# DebounceEncoder.net
KiCad netlist of a schematic drawn in EAGLE
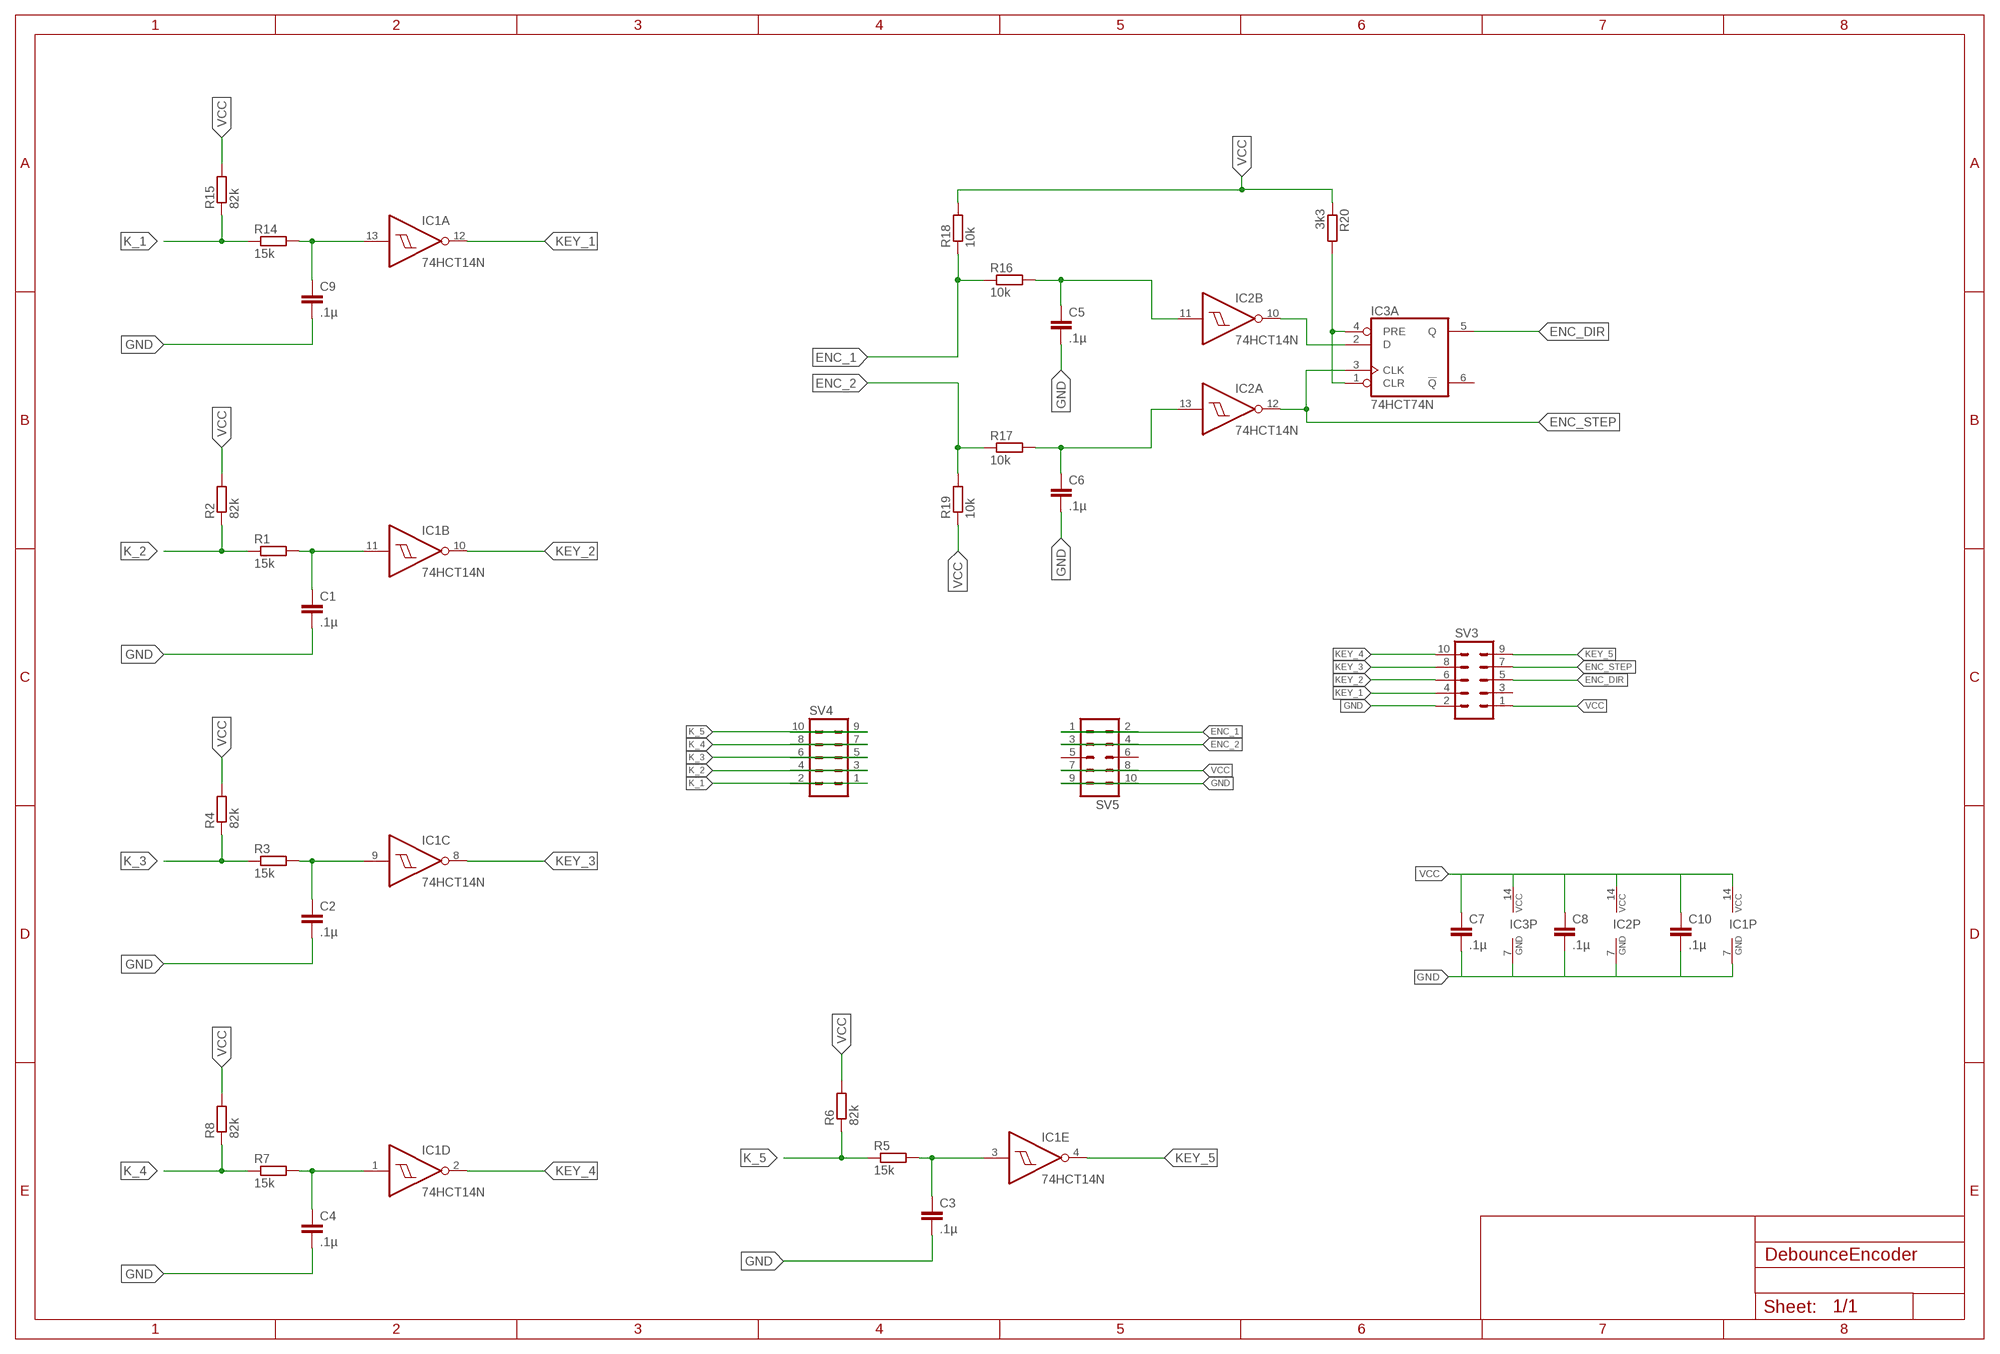
[diagram p0: schematic, sheet 1]

(export (version "E")
  (design (tool "Eeschema 10.0.6"))
  (components
    (comp (ref "C1")
      (value ".1µ")
      (footprint "eagle-import:C025-024X044")
      (libsource (lib "eagle-import") (part "C-EU025-024X044"))
    )
    (comp (ref "C2")
      (value ".1µ")
      (footprint "eagle-import:C025-024X044")
      (libsource (lib "eagle-import") (part "C-EU025-024X044"))
    )
    (comp (ref "C3")
      (value ".1µ")
      (footprint "eagle-import:C025-024X044")
      (libsource (lib "eagle-import") (part "C-EU025-024X044"))
    )
    (comp (ref "C4")
      (value ".1µ")
      (footprint "eagle-import:C025-024X044")
      (libsource (lib "eagle-import") (part "C-EU025-024X044"))
    )
    (comp (ref "C5")
      (value ".1µ")
      (footprint "eagle-import:C025-024X044")
      (libsource (lib "eagle-import") (part "C-EU025-024X044"))
    )
    (comp (ref "C6")
      (value ".1µ")
      (footprint "eagle-import:C025-024X044")
      (libsource (lib "eagle-import") (part "C-EU025-024X044"))
    )
    (comp (ref "C7")
      (value ".1µ")
      (footprint "eagle-import:C025-024X044")
      (libsource (lib "eagle-import") (part "C-EU025-024X044"))
    )
    (comp (ref "C8")
      (value ".1µ")
      (footprint "eagle-import:C025-024X044")
      (libsource (lib "eagle-import") (part "C-EU025-024X044"))
    )
    (comp (ref "C9")
      (value ".1µ")
      (footprint "eagle-import:C025-024X044")
      (libsource (lib "eagle-import") (part "C-EU025-024X044"))
    )
    (comp (ref "C10")
      (value ".1µ")
      (footprint "eagle-import:C025-024X044")
      (libsource (lib "eagle-import") (part "C-EU025-024X044"))
    )
    (comp (ref "IC1")
      (value "74HCT14N")
      (footprint "eagle-import:DIL14")
      (libsource (lib "eagle-import") (part "7414NHCT"))
    )
    (comp (ref "IC2")
      (value "74HCT14N")
      (footprint "eagle-import:DIL14")
      (libsource (lib "eagle-import") (part "7414NHCT"))
    )
    (comp (ref "IC3")
      (value "74HCT74N")
      (footprint "eagle-import:DIL14")
      (libsource (lib "eagle-import") (part "7474NHCT"))
    )
    (comp (ref "R1")
      (value "15k")
      (footprint "eagle-import:0204_7")
      (libsource (lib "eagle-import") (part "R-EU_0204/7"))
    )
    (comp (ref "R2")
      (value "82k")
      (footprint "eagle-import:0204_7")
      (libsource (lib "eagle-import") (part "R-EU_0204/7"))
    )
    (comp (ref "R3")
      (value "15k")
      (footprint "eagle-import:0204_7")
      (libsource (lib "eagle-import") (part "R-EU_0204/7"))
    )
    (comp (ref "R4")
      (value "82k")
      (footprint "eagle-import:0204_7")
      (libsource (lib "eagle-import") (part "R-EU_0204/7"))
    )
    (comp (ref "R5")
      (value "15k")
      (footprint "eagle-import:0204_7")
      (libsource (lib "eagle-import") (part "R-EU_0204/7"))
    )
    (comp (ref "R6")
      (value "82k")
      (footprint "eagle-import:0204_7")
      (libsource (lib "eagle-import") (part "R-EU_0204/7"))
    )
    (comp (ref "R7")
      (value "15k")
      (footprint "eagle-import:0204_7")
      (libsource (lib "eagle-import") (part "R-EU_0204/7"))
    )
    (comp (ref "R8")
      (value "82k")
      (footprint "eagle-import:0204_7")
      (libsource (lib "eagle-import") (part "R-EU_0204/7"))
    )
    (comp (ref "R14")
      (value "15k")
      (footprint "eagle-import:0204_7")
      (libsource (lib "eagle-import") (part "R-EU_0204/7"))
    )
    (comp (ref "R15")
      (value "82k")
      (footprint "eagle-import:0204_7")
      (libsource (lib "eagle-import") (part "R-EU_0204/7"))
    )
    (comp (ref "R16")
      (value "10k")
      (footprint "eagle-import:0204_7")
      (libsource (lib "eagle-import") (part "R-EU_0204/7"))
    )
    (comp (ref "R17")
      (value "10k")
      (footprint "eagle-import:0204_7")
      (libsource (lib "eagle-import") (part "R-EU_0204/7"))
    )
    (comp (ref "R18")
      (value "10k")
      (footprint "eagle-import:0204_7")
      (libsource (lib "eagle-import") (part "R-EU_0204/7"))
    )
    (comp (ref "R19")
      (value "10k")
      (footprint "eagle-import:0204_7")
      (libsource (lib "eagle-import") (part "R-EU_0204/7"))
    )
    (comp (ref "R20")
      (value "3k3")
      (footprint "eagle-import:0204_7")
      (libsource (lib "eagle-import") (part "R-EU_0204/7"))
    )
    (comp (ref "SV3")
      (value "ML10L")
      (footprint "eagle-import:ML10L")
      (libsource (lib "eagle-import") (part "ML10L"))
    )
    (comp (ref "SV4")
      (value "MA05-2")
      (footprint "eagle-import:MA05-2")
      (libsource (lib "eagle-import") (part "MA05-2"))
    )
    (comp (ref "SV5")
      (value "MA05-2")
      (footprint "eagle-import:MA05-2")
      (libsource (lib "eagle-import") (part "MA05-2"))
    )
  )
  (nets
    (net (code "1") (name "ENC_1") (class "Default")
      (node (ref "R16") (pin "1") (pinfunction "1_1") (pintype "passive"))
      (node (ref "R18") (pin "1") (pinfunction "1_1") (pintype "passive"))
      (node (ref "SV5") (pin "1") (pinfunction "1_1") (pintype "passive"))
      (node (ref "SV5") (pin "2") (pinfunction "2_2") (pintype "passive"))
    )
    (net (code "2") (name "ENC_2") (class "Default")
      (node (ref "R17") (pin "1") (pinfunction "1_1") (pintype "passive"))
      (node (ref "R19") (pin "2") (pinfunction "2_2") (pintype "passive"))
      (node (ref "SV5") (pin "3") (pinfunction "3_3") (pintype "passive"))
      (node (ref "SV5") (pin "4") (pinfunction "4_4") (pintype "passive"))
    )
    (net (code "3") (name "ENC_DIR") (class "Default")
      (node (ref "IC3") (pin "5") (pinfunction "Q_5") (pintype "output"))
      (node (ref "SV3") (pin "5") (pinfunction "5_5") (pintype "passive"))
    )
    (net (code "4") (name "ENC_STEP") (class "Default")
      (node (ref "IC2") (pin "12") (pinfunction "O_12") (pintype "output"))
      (node (ref "IC3") (pin "3") (pinfunction "CLK_3") (pintype "input"))
      (node (ref "SV3") (pin "7") (pinfunction "7_7") (pintype "passive"))
    )
    (net (code "5") (name "GND") (class "Default")
      (node (ref "C1") (pin "2") (pinfunction "2_2") (pintype "passive"))
      (node (ref "C10") (pin "2") (pinfunction "2_2") (pintype "passive"))
      (node (ref "C2") (pin "2") (pinfunction "2_2") (pintype "passive"))
      (node (ref "C3") (pin "2") (pinfunction "2_2") (pintype "passive"))
      (node (ref "C4") (pin "2") (pinfunction "2_2") (pintype "passive"))
      (node (ref "C5") (pin "2") (pinfunction "2_2") (pintype "passive"))
      (node (ref "C6") (pin "2") (pinfunction "2_2") (pintype "passive"))
      (node (ref "C7") (pin "2") (pinfunction "2_2") (pintype "passive"))
      (node (ref "C8") (pin "2") (pinfunction "2_2") (pintype "passive"))
      (node (ref "C9") (pin "2") (pinfunction "2_2") (pintype "passive"))
      (node (ref "IC1") (pin "7") (pinfunction "GND_7") (pintype "power_in"))
      (node (ref "IC2") (pin "7") (pinfunction "GND_7") (pintype "power_in"))
      (node (ref "IC3") (pin "7") (pinfunction "GND_7") (pintype "power_in"))
      (node (ref "SV3") (pin "2") (pinfunction "2_2") (pintype "passive"))
      (node (ref "SV5") (pin "10") (pinfunction "10_10") (pintype "passive"))
      (node (ref "SV5") (pin "9") (pinfunction "9_9") (pintype "passive"))
    )
    (net (code "6") (name "KEY_1") (class "Default")
      (node (ref "IC1") (pin "12") (pinfunction "O_12") (pintype "output"))
      (node (ref "SV3") (pin "4") (pinfunction "4_4") (pintype "passive"))
    )
    (net (code "7") (name "KEY_2") (class "Default")
      (node (ref "IC1") (pin "10") (pinfunction "O_10") (pintype "output"))
      (node (ref "SV3") (pin "6") (pinfunction "6_6") (pintype "passive"))
    )
    (net (code "8") (name "KEY_3") (class "Default")
      (node (ref "IC1") (pin "8") (pinfunction "O_8") (pintype "output"))
      (node (ref "SV3") (pin "8") (pinfunction "8_8") (pintype "passive"))
    )
    (net (code "9") (name "KEY_4") (class "Default")
      (node (ref "IC1") (pin "2") (pinfunction "O_2") (pintype "output"))
      (node (ref "SV3") (pin "10") (pinfunction "10_10") (pintype "passive"))
    )
    (net (code "10") (name "KEY_5") (class "Default")
      (node (ref "IC1") (pin "4") (pinfunction "O_4") (pintype "output"))
      (node (ref "SV3") (pin "9") (pinfunction "9_9") (pintype "passive"))
    )
    (net (code "11") (name "K_1") (class "Default")
      (node (ref "R14") (pin "1") (pinfunction "1_1") (pintype "passive"))
      (node (ref "R15") (pin "1") (pinfunction "1_1") (pintype "passive"))
      (node (ref "SV4") (pin "1") (pinfunction "1_1") (pintype "passive"))
      (node (ref "SV4") (pin "2") (pinfunction "2_2") (pintype "passive"))
    )
    (net (code "12") (name "K_2") (class "Default")
      (node (ref "R1") (pin "1") (pinfunction "1_1") (pintype "passive"))
      (node (ref "R2") (pin "1") (pinfunction "1_1") (pintype "passive"))
      (node (ref "SV4") (pin "3") (pinfunction "3_3") (pintype "passive"))
      (node (ref "SV4") (pin "4") (pinfunction "4_4") (pintype "passive"))
    )
    (net (code "13") (name "K_3") (class "Default")
      (node (ref "R3") (pin "1") (pinfunction "1_1") (pintype "passive"))
      (node (ref "R4") (pin "1") (pinfunction "1_1") (pintype "passive"))
      (node (ref "SV4") (pin "5") (pinfunction "5_5") (pintype "passive"))
      (node (ref "SV4") (pin "6") (pinfunction "6_6") (pintype "passive"))
    )
    (net (code "14") (name "K_4") (class "Default")
      (node (ref "R7") (pin "1") (pinfunction "1_1") (pintype "passive"))
      (node (ref "R8") (pin "1") (pinfunction "1_1") (pintype "passive"))
      (node (ref "SV4") (pin "7") (pinfunction "7_7") (pintype "passive"))
      (node (ref "SV4") (pin "8") (pinfunction "8_8") (pintype "passive"))
    )
    (net (code "15") (name "K_5") (class "Default")
      (node (ref "R5") (pin "1") (pinfunction "1_1") (pintype "passive"))
      (node (ref "R6") (pin "1") (pinfunction "1_1") (pintype "passive"))
      (node (ref "SV4") (pin "10") (pinfunction "10_10") (pintype "passive"))
      (node (ref "SV4") (pin "9") (pinfunction "9_9") (pintype "passive"))
    )
    (net (code "16") (name "Net-(IC1A-I)") (class "Default")
      (node (ref "C9") (pin "1") (pinfunction "1_1") (pintype "passive"))
      (node (ref "IC1") (pin "13") (pinfunction "I_13") (pintype "input"))
      (node (ref "R14") (pin "2") (pinfunction "2_2") (pintype "passive"))
    )
    (net (code "17") (name "Net-(IC1B-I)") (class "Default")
      (node (ref "C1") (pin "1") (pinfunction "1_1") (pintype "passive"))
      (node (ref "IC1") (pin "11") (pinfunction "I_11") (pintype "input"))
      (node (ref "R1") (pin "2") (pinfunction "2_2") (pintype "passive"))
    )
    (net (code "18") (name "Net-(IC1C-I)") (class "Default")
      (node (ref "C2") (pin "1") (pinfunction "1_1") (pintype "passive"))
      (node (ref "IC1") (pin "9") (pinfunction "I_9") (pintype "input"))
      (node (ref "R3") (pin "2") (pinfunction "2_2") (pintype "passive"))
    )
    (net (code "19") (name "Net-(IC1D-I)") (class "Default")
      (node (ref "C4") (pin "1") (pinfunction "1_1") (pintype "passive"))
      (node (ref "IC1") (pin "1") (pinfunction "I_1") (pintype "input"))
      (node (ref "R7") (pin "2") (pinfunction "2_2") (pintype "passive"))
    )
    (net (code "20") (name "Net-(IC1E-I)") (class "Default")
      (node (ref "C3") (pin "1") (pinfunction "1_1") (pintype "passive"))
      (node (ref "IC1") (pin "3") (pinfunction "I_3") (pintype "input"))
      (node (ref "R5") (pin "2") (pinfunction "2_2") (pintype "passive"))
    )
    (net (code "21") (name "Net-(IC2A-I)") (class "Default")
      (node (ref "C6") (pin "1") (pinfunction "1_1") (pintype "passive"))
      (node (ref "IC2") (pin "13") (pinfunction "I_13") (pintype "input"))
      (node (ref "R17") (pin "2") (pinfunction "2_2") (pintype "passive"))
    )
    (net (code "22") (name "Net-(IC2B-I)") (class "Default")
      (node (ref "C5") (pin "1") (pinfunction "1_1") (pintype "passive"))
      (node (ref "IC2") (pin "11") (pinfunction "I_11") (pintype "input"))
      (node (ref "R16") (pin "2") (pinfunction "2_2") (pintype "passive"))
    )
    (net (code "23") (name "Net-(IC2B-O)") (class "Default")
      (node (ref "IC2") (pin "10") (pinfunction "O_10") (pintype "output"))
      (node (ref "IC3") (pin "2") (pinfunction "D_2") (pintype "input"))
    )
    (net (code "24") (name "Net-(IC3A-CLR)") (class "Default")
      (node (ref "IC3") (pin "1") (pinfunction "CLR_1") (pintype "input"))
      (node (ref "IC3") (pin "4") (pinfunction "PRE_4") (pintype "input"))
      (node (ref "R20") (pin "2") (pinfunction "2_2") (pintype "passive"))
    )
    (net (code "25") (name "VCC") (class "Default")
      (node (ref "C10") (pin "1") (pinfunction "1_1") (pintype "passive"))
      (node (ref "C7") (pin "1") (pinfunction "1_1") (pintype "passive"))
      (node (ref "C8") (pin "1") (pinfunction "1_1") (pintype "passive"))
      (node (ref "IC1") (pin "14") (pinfunction "VCC_14") (pintype "power_in"))
      (node (ref "IC2") (pin "14") (pinfunction "VCC_14") (pintype "power_in"))
      (node (ref "IC3") (pin "14") (pinfunction "VCC_14") (pintype "power_in"))
      (node (ref "R15") (pin "2") (pinfunction "2_2") (pintype "passive"))
      (node (ref "R18") (pin "2") (pinfunction "2_2") (pintype "passive"))
      (node (ref "R19") (pin "1") (pinfunction "1_1") (pintype "passive"))
      (node (ref "R2") (pin "2") (pinfunction "2_2") (pintype "passive"))
      (node (ref "R20") (pin "1") (pinfunction "1_1") (pintype "passive"))
      (node (ref "R4") (pin "2") (pinfunction "2_2") (pintype "passive"))
      (node (ref "R6") (pin "2") (pinfunction "2_2") (pintype "passive"))
      (node (ref "R8") (pin "2") (pinfunction "2_2") (pintype "passive"))
      (node (ref "SV3") (pin "1") (pinfunction "1_1") (pintype "passive"))
      (node (ref "SV5") (pin "7") (pinfunction "7_7") (pintype "passive"))
      (node (ref "SV5") (pin "8") (pinfunction "8_8") (pintype "passive"))
    )
    (net (code "26") (name "unconnected-(IC3A-~{Q}-Pad6)") (class "Default")
      (node (ref "IC3") (pin "6") (pinfunction "~{Q}_6") (pintype "output"))
    )
    (net (code "27") (name "unconnected-(SV3-Pad3)") (class "Default")
      (node (ref "SV3") (pin "3") (pinfunction "3_3") (pintype "passive"))
    )
    (net (code "28") (name "unconnected-(SV5-Pad5)") (class "Default")
      (node (ref "SV5") (pin "5") (pinfunction "5_5") (pintype "passive"))
    )
    (net (code "29") (name "unconnected-(SV5-Pad6)") (class "Default")
      (node (ref "SV5") (pin "6") (pinfunction "6_6") (pintype "passive"))
    )
  )
)
